# untitled.net
KiCad netlist of a schematic drawn in EAGLE
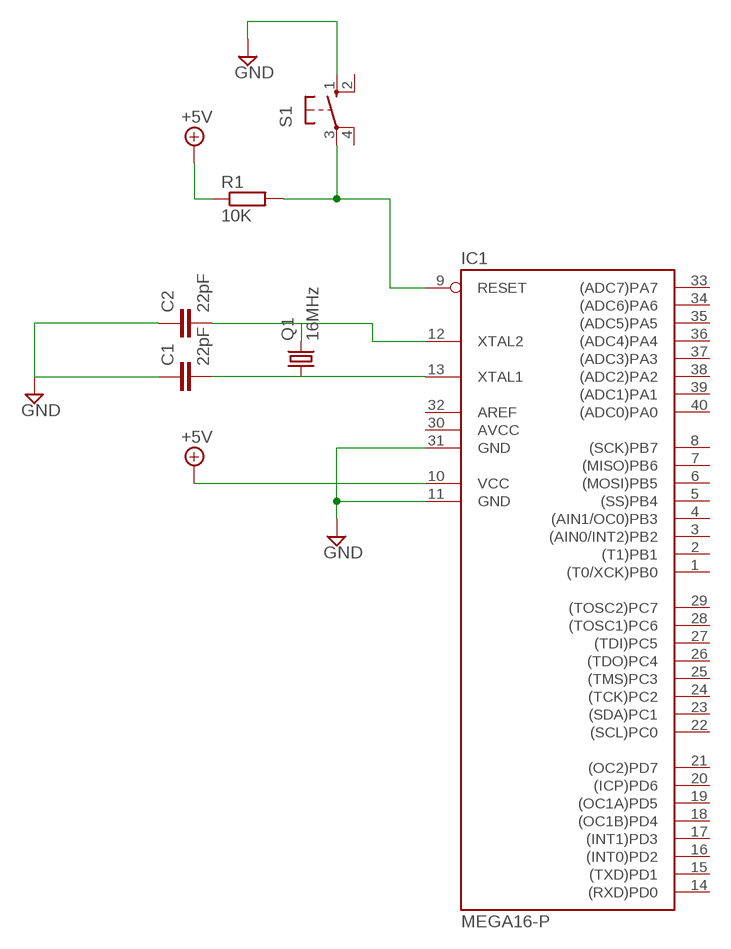
[diagram p0: schematic, sheet 1]

(export (version "E")
  (design (tool "Eeschema 10.0.6"))
  (components
    (comp (ref "C1")
      (value "22pF")
      (footprint "eagle-import:C025-025X050")
      (libsource (lib "eagle-import") (part "C-EU025-025X050"))
    )
    (comp (ref "C2")
      (value "22pF")
      (footprint "eagle-import:C025-025X050")
      (libsource (lib "eagle-import") (part "C-EU025-025X050"))
    )
    (comp (ref "IC1")
      (value "MEGA16-P")
      (footprint "eagle-import:DIL40")
      (fields (field (name "MPN") "ATMEGA16-16PU"))
      (libsource (lib "eagle-import") (part "MEGA16-P"))
    )
    (comp (ref "Q1")
      (value "16MHz")
      (footprint "eagle-import:HC49_S")
      (libsource (lib "eagle-import") (part "CRYSTALHC49S"))
    )
    (comp (ref "R1")
      (value "10K")
      (footprint "eagle-import:0204_7")
      (libsource (lib "eagle-import") (part "R-EU_0204/7"))
    )
    (comp (ref "S1")
      (value "10-XX")
      (footprint "eagle-import:B3F-10XX")
      (fields (field (name "MPN") "B3F-1000"))
      (libsource (lib "eagle-import") (part "10-XX"))
    )
  )
  (nets
    (net (code "1") (name "+5V") (class "Default")
      (node (ref "IC1") (pin "10") (pinfunction "VCC_10") (pintype "power_in"))
      (node (ref "R1") (pin "1") (pinfunction "1_1") (pintype "passive"))
    )
    (net (code "2") (name "/AVCC") (class "Default")
      (node (ref "IC1") (pin "30") (pinfunction "AVCC_30") (pintype "power_in"))
    )
    (net (code "3") (name "GND") (class "Default")
      (node (ref "C1") (pin "1") (pinfunction "1_1") (pintype "passive"))
      (node (ref "C2") (pin "1") (pinfunction "1_1") (pintype "passive"))
      (node (ref "IC1") (pin "11") (pinfunction "GND_11") (pintype "power_in"))
      (node (ref "IC1") (pin "31") (pinfunction "GND_31") (pintype "power_in"))
      (node (ref "S1") (pin "1") (pinfunction "S_1") (pintype "passive"))
    )
    (net (code "4") (name "Net-(IC1-RESET)") (class "Default")
      (node (ref "IC1") (pin "9") (pinfunction "RESET_9") (pintype "input"))
      (node (ref "R1") (pin "2") (pinfunction "2_2") (pintype "passive"))
      (node (ref "S1") (pin "3") (pinfunction "P_3") (pintype "passive"))
    )
    (net (code "5") (name "Net-(IC1-XTAL1)") (class "Default")
      (node (ref "C1") (pin "2") (pinfunction "2_2") (pintype "passive"))
      (node (ref "IC1") (pin "13") (pinfunction "XTAL1_13") (pintype "bidirectional"))
      (node (ref "Q1") (pin "1") (pinfunction "1_1") (pintype "passive"))
    )
    (net (code "6") (name "Net-(IC1-XTAL2)") (class "Default")
      (node (ref "C2") (pin "2") (pinfunction "2_2") (pintype "passive"))
      (node (ref "IC1") (pin "12") (pinfunction "XTAL2_12") (pintype "bidirectional"))
      (node (ref "Q1") (pin "2") (pinfunction "2_2") (pintype "passive"))
    )
    (net (code "7") (name "unconnected-(IC1-(ADC0)PA0-Pad40)") (class "Default")
      (node (ref "IC1") (pin "40") (pinfunction "(ADC0)PA0_40") (pintype "bidirectional"))
    )
    (net (code "8") (name "unconnected-(IC1-(ADC1)PA1-Pad39)") (class "Default")
      (node (ref "IC1") (pin "39") (pinfunction "(ADC1)PA1_39") (pintype "bidirectional"))
    )
    (net (code "9") (name "unconnected-(IC1-(ADC2)PA2-Pad38)") (class "Default")
      (node (ref "IC1") (pin "38") (pinfunction "(ADC2)PA2_38") (pintype "bidirectional"))
    )
    (net (code "10") (name "unconnected-(IC1-(ADC3)PA3-Pad37)") (class "Default")
      (node (ref "IC1") (pin "37") (pinfunction "(ADC3)PA3_37") (pintype "bidirectional"))
    )
    (net (code "11") (name "unconnected-(IC1-(ADC4)PA4-Pad36)") (class "Default")
      (node (ref "IC1") (pin "36") (pinfunction "(ADC4)PA4_36") (pintype "bidirectional"))
    )
    (net (code "12") (name "unconnected-(IC1-(ADC5)PA5-Pad35)") (class "Default")
      (node (ref "IC1") (pin "35") (pinfunction "(ADC5)PA5_35") (pintype "bidirectional"))
    )
    (net (code "13") (name "unconnected-(IC1-(ADC6)PA6-Pad34)") (class "Default")
      (node (ref "IC1") (pin "34") (pinfunction "(ADC6)PA6_34") (pintype "bidirectional"))
    )
    (net (code "14") (name "unconnected-(IC1-(ADC7)PA7-Pad33)") (class "Default")
      (node (ref "IC1") (pin "33") (pinfunction "(ADC7)PA7_33") (pintype "bidirectional"))
    )
    (net (code "15") (name "unconnected-(IC1-(AIN0{slash}INT2)PB2-Pad3)") (class "Default")
      (node (ref "IC1") (pin "3") (pinfunction "(AIN0/INT2)PB2_3") (pintype "bidirectional"))
    )
    (net (code "16") (name "unconnected-(IC1-(AIN1{slash}OC0)PB3-Pad4)") (class "Default")
      (node (ref "IC1") (pin "4") (pinfunction "(AIN1/OC0)PB3_4") (pintype "bidirectional"))
    )
    (net (code "17") (name "unconnected-(IC1-(ICP)PD6-Pad20)") (class "Default")
      (node (ref "IC1") (pin "20") (pinfunction "(ICP)PD6_20") (pintype "bidirectional"))
    )
    (net (code "18") (name "unconnected-(IC1-(INT0)PD2-Pad16)") (class "Default")
      (node (ref "IC1") (pin "16") (pinfunction "(INT0)PD2_16") (pintype "bidirectional"))
    )
    (net (code "19") (name "unconnected-(IC1-(INT1)PD3-Pad17)") (class "Default")
      (node (ref "IC1") (pin "17") (pinfunction "(INT1)PD3_17") (pintype "bidirectional"))
    )
    (net (code "20") (name "unconnected-(IC1-(MISO)PB6-Pad7)") (class "Default")
      (node (ref "IC1") (pin "7") (pinfunction "(MISO)PB6_7") (pintype "bidirectional"))
    )
    (net (code "21") (name "unconnected-(IC1-(MOSI)PB5-Pad6)") (class "Default")
      (node (ref "IC1") (pin "6") (pinfunction "(MOSI)PB5_6") (pintype "bidirectional"))
    )
    (net (code "22") (name "unconnected-(IC1-(OC1A)PD5-Pad19)") (class "Default")
      (node (ref "IC1") (pin "19") (pinfunction "(OC1A)PD5_19") (pintype "bidirectional"))
    )
    (net (code "23") (name "unconnected-(IC1-(OC1B)PD4-Pad18)") (class "Default")
      (node (ref "IC1") (pin "18") (pinfunction "(OC1B)PD4_18") (pintype "bidirectional"))
    )
    (net (code "24") (name "unconnected-(IC1-(OC2)PD7-Pad21)") (class "Default")
      (node (ref "IC1") (pin "21") (pinfunction "(OC2)PD7_21") (pintype "bidirectional"))
    )
    (net (code "25") (name "unconnected-(IC1-(RXD)PD0-Pad14)") (class "Default")
      (node (ref "IC1") (pin "14") (pinfunction "(RXD)PD0_14") (pintype "bidirectional"))
    )
    (net (code "26") (name "unconnected-(IC1-(SCK)PB7-Pad8)") (class "Default")
      (node (ref "IC1") (pin "8") (pinfunction "(SCK)PB7_8") (pintype "bidirectional"))
    )
    (net (code "27") (name "unconnected-(IC1-(SCL)PC0-Pad22)") (class "Default")
      (node (ref "IC1") (pin "22") (pinfunction "(SCL)PC0_22") (pintype "bidirectional"))
    )
    (net (code "28") (name "unconnected-(IC1-(SDA)PC1-Pad23)") (class "Default")
      (node (ref "IC1") (pin "23") (pinfunction "(SDA)PC1_23") (pintype "bidirectional"))
    )
    (net (code "29") (name "unconnected-(IC1-(SS)PB4-Pad5)") (class "Default")
      (node (ref "IC1") (pin "5") (pinfunction "(SS)PB4_5") (pintype "bidirectional"))
    )
    (net (code "30") (name "unconnected-(IC1-(T0{slash}XCK)PB0-Pad1)") (class "Default")
      (node (ref "IC1") (pin "1") (pinfunction "(T0/XCK)PB0_1") (pintype "bidirectional"))
    )
    (net (code "31") (name "unconnected-(IC1-(T1)PB1-Pad2)") (class "Default")
      (node (ref "IC1") (pin "2") (pinfunction "(T1)PB1_2") (pintype "bidirectional"))
    )
    (net (code "32") (name "unconnected-(IC1-(TCK)PC2-Pad24)") (class "Default")
      (node (ref "IC1") (pin "24") (pinfunction "(TCK)PC2_24") (pintype "bidirectional"))
    )
    (net (code "33") (name "unconnected-(IC1-(TDI)PC5-Pad27)") (class "Default")
      (node (ref "IC1") (pin "27") (pinfunction "(TDI)PC5_27") (pintype "bidirectional"))
    )
    (net (code "34") (name "unconnected-(IC1-(TDO)PC4-Pad26)") (class "Default")
      (node (ref "IC1") (pin "26") (pinfunction "(TDO)PC4_26") (pintype "bidirectional"))
    )
    (net (code "35") (name "unconnected-(IC1-(TMS)PC3-Pad25)") (class "Default")
      (node (ref "IC1") (pin "25") (pinfunction "(TMS)PC3_25") (pintype "bidirectional"))
    )
    (net (code "36") (name "unconnected-(IC1-(TOSC1)PC6-Pad28)") (class "Default")
      (node (ref "IC1") (pin "28") (pinfunction "(TOSC1)PC6_28") (pintype "bidirectional"))
    )
    (net (code "37") (name "unconnected-(IC1-(TOSC2)PC7-Pad29)") (class "Default")
      (node (ref "IC1") (pin "29") (pinfunction "(TOSC2)PC7_29") (pintype "bidirectional"))
    )
    (net (code "38") (name "unconnected-(IC1-(TXD)PD1-Pad15)") (class "Default")
      (node (ref "IC1") (pin "15") (pinfunction "(TXD)PD1_15") (pintype "bidirectional"))
    )
    (net (code "39") (name "unconnected-(IC1-AREF-Pad32)") (class "Default")
      (node (ref "IC1") (pin "32") (pinfunction "AREF_32") (pintype "passive"))
    )
    (net (code "40") (name "unconnected-(S1-P1-Pad4)") (class "Default")
      (node (ref "S1") (pin "4") (pinfunction "P1_4") (pintype "passive"))
    )
    (net (code "41") (name "unconnected-(S1-S1-Pad2)") (class "Default")
      (node (ref "S1") (pin "2") (pinfunction "S1_2") (pintype "passive"))
    )
  )
)
